# Connectors.net
KiCad netlist of a schematic drawn in Altium Designer
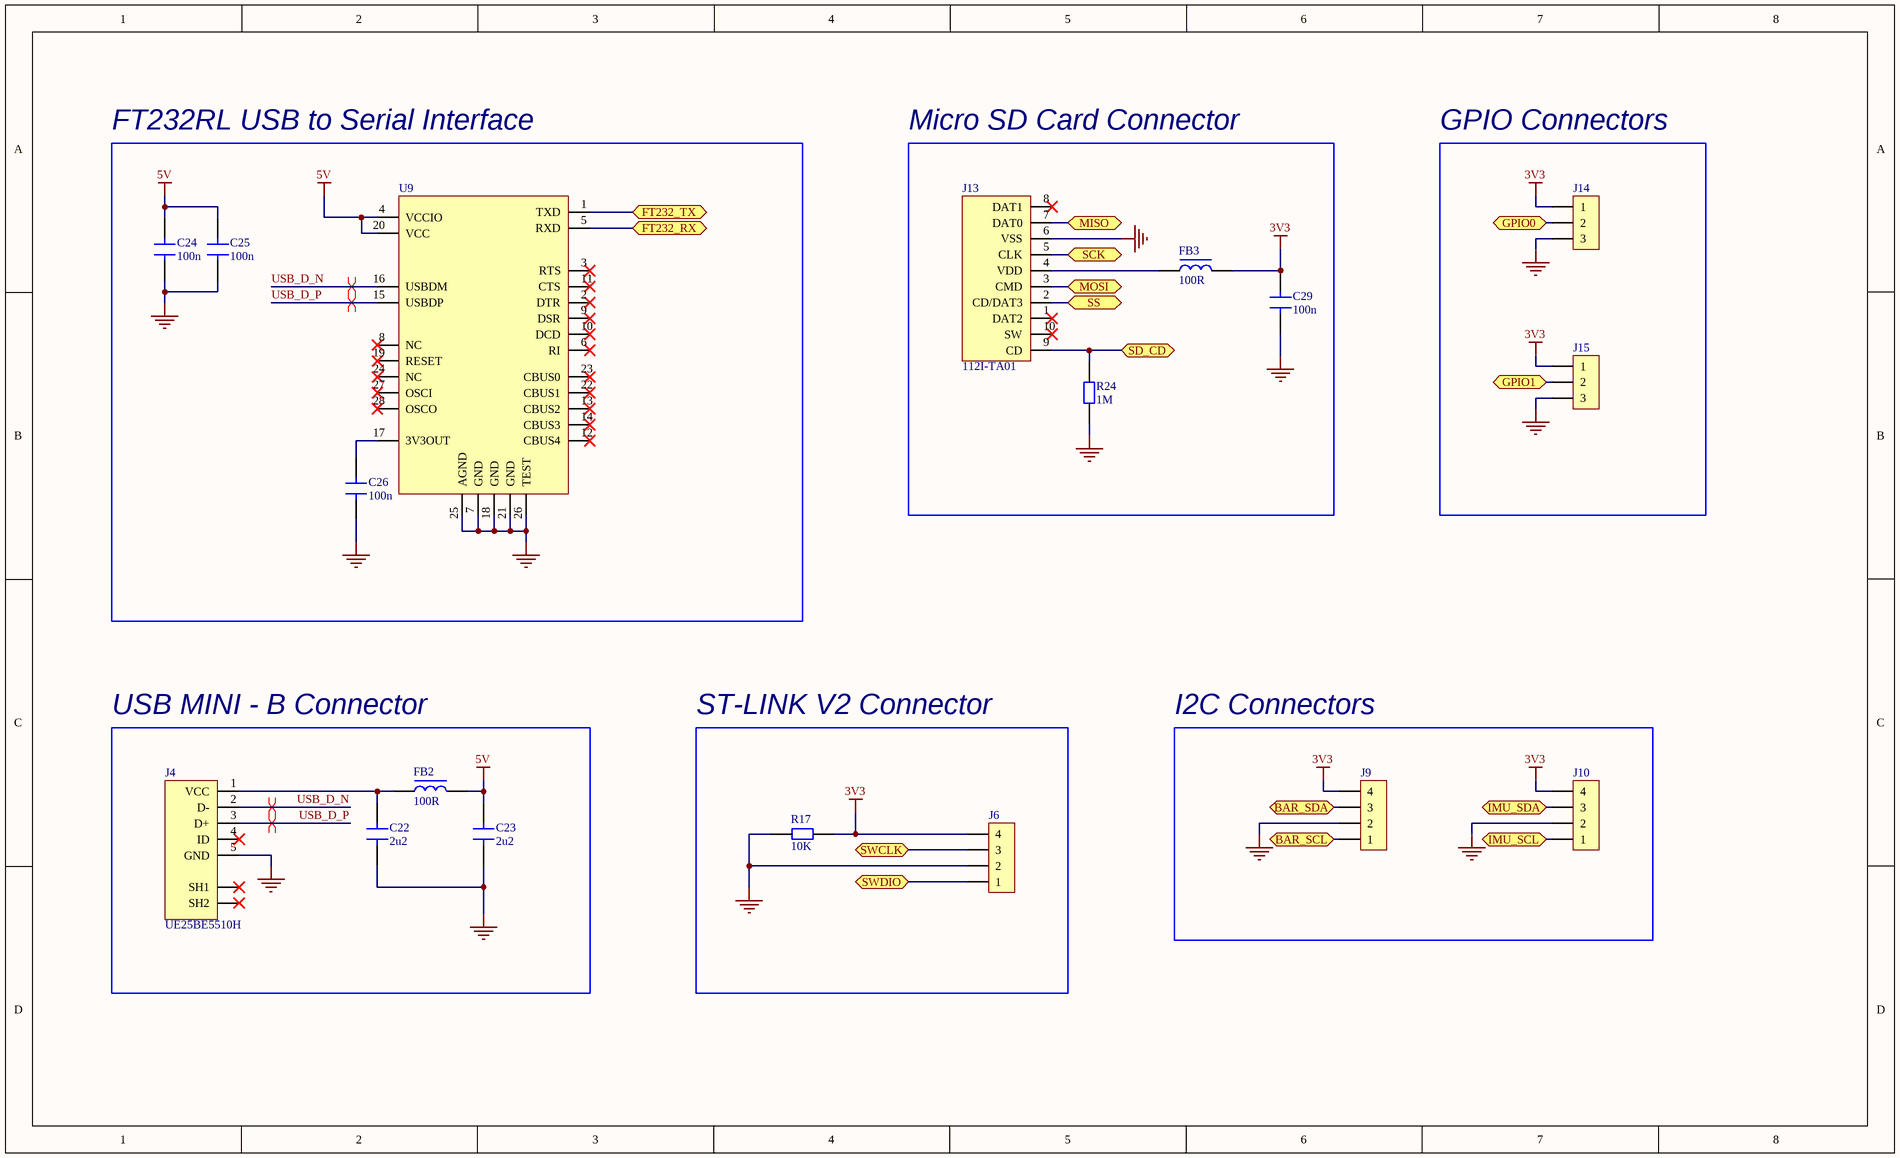
[diagram p0: Connectors.SchDoc]

(export (version "E")
  (design (tool "Eeschema 10.0.6"))
  (components
    (comp (ref "C22")
      (value "2u2")
      (footprint "CAP 0805")
      (description "Capacitor SMD 0805 25V")
      (libsource (lib "Schlib") (part "CAP 0805 25V"))
    )
    (comp (ref "C23")
      (value "2u2")
      (footprint "CAP 0805")
      (description "Capacitor SMD 0805 25V")
      (libsource (lib "Schlib") (part "CAP 0805 25V"))
    )
    (comp (ref "C24")
      (value "100n")
      (footprint "CAP 0603")
      (description "Capacitor SMD 0603 50V")
      (libsource (lib "Schlib") (part "CAP 0603 50V"))
    )
    (comp (ref "C25")
      (value "100n")
      (footprint "CAP 0603")
      (description "Capacitor SMD 0603 50V")
      (libsource (lib "Schlib") (part "CAP 0603 50V"))
    )
    (comp (ref "C26")
      (value "100n")
      (footprint "CAP 0603")
      (description "Capacitor SMD 0603 50V")
      (libsource (lib "Schlib") (part "CAP 0603 50V"))
    )
    (comp (ref "C29")
      (value "100n")
      (footprint "CAP 0603")
      (description "Capacitor SMD 0603 50V")
      (libsource (lib "Schlib") (part "CAP 0603 50V"))
    )
    (comp (ref "FB2")
      (value "100R")
      (footprint "FB 0805")
      (description "Ferrite Bead SMD 0805")
      (libsource (lib "Schlib") (part "FB 0805"))
    )
    (comp (ref "FB3")
      (value "100R")
      (footprint "FB 0603")
      (description "Ferrite Bead SMD 0603")
      (libsource (lib "Schlib") (part "FB 0603"))
    )
    (comp (ref "J4")
      (value "UE25BE5510H")
      (footprint "UE25BE55H")
      (description "Conn Mini USB 2.0 Type B RCP 5 POS 0.8mm Solder ST Thru-Hole 5 Terminal 1 Port")
      (fields (field (name "MANUFACTURER") "Amphenol Commercial"))
      (libsource (lib "Schlib") (part "UE25BE5510H"))
    )
    (comp (ref "J6")
      (value "1x4 HEADER MALE")
      (footprint "1X4 HEADER MALE")
      (libsource (lib "Schlib") (part "1x4 HEADER MALE"))
    )
    (comp (ref "J9")
      (value "1x4 HEADER MALE")
      (footprint "1X4 HEADER MALE")
      (libsource (lib "Schlib") (part "1x4 HEADER MALE"))
    )
    (comp (ref "J10")
      (value "1x4 HEADER MALE")
      (footprint "1X4 HEADER MALE")
      (libsource (lib "Schlib") (part "1x4 HEADER MALE"))
    )
    (comp (ref "J13")
      (value "112I-TA01")
      (footprint "112I-TA01")
      (description "Micro SD Card Push-Pull 10P (8+2), Switch, Peg, SMD 112I-TA01")
      (libsource (lib "Schlib") (part "112I-TA01"))
    )
    (comp (ref "J14")
      (value "JST B3B-XH-A")
      (footprint "JST_B3B-XH-A")
      (description "Connector Header, XH Series, 3 Position, 2.50mm, Through Hole, Press-Fit, Solder, Natural")
      (fields
        (field (name "MANUFACTURER") "JST")
        (field (name "MANUFACTURER PART NUMBER") "B3B-XH-A(LF)(SN)")
      )
      (libsource (lib "Schlib") (part "JST B3B-XH-A"))
    )
    (comp (ref "J15")
      (value "JST B3B-XH-A")
      (footprint "JST_B3B-XH-A")
      (description "Connector Header, XH Series, 3 Position, 2.50mm, Through Hole, Press-Fit, Solder, Natural")
      (fields
        (field (name "MANUFACTURER") "JST")
        (field (name "MANUFACTURER PART NUMBER") "B3B-XH-A(LF)(SN)")
      )
      (libsource (lib "Schlib") (part "JST B3B-XH-A"))
    )
    (comp (ref "R17")
      (value "10K")
      (footprint "RES 0603")
      (description "Resistor SMD 0603")
      (libsource (lib "Schlib") (part "RES 0603"))
    )
    (comp (ref "R24")
      (value "1M")
      (footprint "RES 0603")
      (description "Resistor SMD 0603")
      (libsource (lib "Schlib") (part "RES 0603"))
    )
    (comp (ref "U9")
      (value "FT232RL-REEL")
      (footprint "FT232RL")
      (description "IC USB FS SERIAL UART 28-SSOP")
      (fields (field (name "MANUFACTURER") "FTDI") (field (name "VOLTAGE") "5V"))
      (libsource (lib "Schlib") (part "FT232RL-REEL"))
    )
  )
  (nets
    (net (code "1") (name "/BAR_SCL") (class "Default")
      (node (ref "J9") (pin "1") (pinfunction "1_1") (pintype "passive"))
    )
    (net (code "2") (name "/BAR_SDA") (class "Default")
      (node (ref "J9") (pin "3") (pinfunction "3_3") (pintype "passive"))
    )
    (net (code "3") (name "/FT232_RX") (class "Default")
      (node (ref "U9") (pin "5") (pinfunction "RXD_5") (pintype "passive"))
    )
    (net (code "4") (name "/FT232_TX") (class "Default")
      (node (ref "U9") (pin "1") (pinfunction "TXD_1") (pintype "passive"))
    )
    (net (code "5") (name "/GPIO0") (class "Default")
      (node (ref "J14") (pin "2") (pinfunction "2_2") (pintype "passive"))
    )
    (net (code "6") (name "/GPIO1") (class "Default")
      (node (ref "J15") (pin "2") (pinfunction "2_2") (pintype "passive"))
    )
    (net (code "7") (name "/IMU_SCL") (class "Default")
      (node (ref "J10") (pin "1") (pinfunction "1_1") (pintype "passive"))
    )
    (net (code "8") (name "/IMU_SDA") (class "Default")
      (node (ref "J10") (pin "3") (pinfunction "3_3") (pintype "passive"))
    )
    (net (code "9") (name "/MISO") (class "Default")
      (node (ref "J13") (pin "7") (pinfunction "DAT0_7") (pintype "passive"))
    )
    (net (code "10") (name "/MOSI") (class "Default")
      (node (ref "J13") (pin "3") (pinfunction "CMD_3") (pintype "passive"))
    )
    (net (code "11") (name "/SCK") (class "Default")
      (node (ref "J13") (pin "5") (pinfunction "CLK_5") (pintype "passive"))
    )
    (net (code "12") (name "/SD_CD") (class "Default")
      (node (ref "J13") (pin "9") (pinfunction "CD_9") (pintype "passive"))
      (node (ref "R24") (pin "2") (pinfunction "2_2") (pintype "passive"))
    )
    (net (code "13") (name "/SS") (class "Default")
      (node (ref "J13") (pin "2") (pinfunction "CD/DAT3_2") (pintype "passive"))
    )
    (net (code "14") (name "/SWCLK") (class "Default")
      (node (ref "J6") (pin "3") (pinfunction "3_3") (pintype "passive"))
    )
    (net (code "15") (name "/SWDIO") (class "Default")
      (node (ref "J6") (pin "1") (pinfunction "1_1") (pintype "passive"))
    )
    (net (code "16") (name "/USB_D_N") (class "Default")
      (node (ref "J4") (pin "2") (pinfunction "D-_2") (pintype "passive"))
      (node (ref "U9") (pin "16") (pinfunction "USBDM_16") (pintype "passive"))
    )
    (net (code "17") (name "/USB_D_P") (class "Default")
      (node (ref "J4") (pin "3") (pinfunction "D+_3") (pintype "passive"))
      (node (ref "U9") (pin "15") (pinfunction "USBDP_15") (pintype "passive"))
    )
    (net (code "18") (name "3V3") (class "Default")
      (node (ref "C29") (pin "2") (pinfunction "2_2") (pintype "passive"))
      (node (ref "FB3") (pin "2") (pintype "passive"))
      (node (ref "J10") (pin "4") (pinfunction "4_4") (pintype "passive"))
      (node (ref "J14") (pin "1") (pinfunction "1_1") (pintype "passive"))
      (node (ref "J15") (pin "1") (pinfunction "1_1") (pintype "passive"))
      (node (ref "J6") (pin "4") (pinfunction "4_4") (pintype "passive"))
      (node (ref "J9") (pin "4") (pinfunction "4_4") (pintype "passive"))
      (node (ref "R17") (pin "2") (pinfunction "2_2") (pintype "passive"))
    )
    (net (code "19") (name "5V") (class "Default")
      (node (ref "C23") (pin "2") (pinfunction "2_2") (pintype "passive"))
      (node (ref "C24") (pin "2") (pinfunction "2_2") (pintype "passive"))
      (node (ref "C25") (pin "2") (pinfunction "2_2") (pintype "passive"))
      (node (ref "FB2") (pin "2") (pintype "passive"))
      (node (ref "U9") (pin "20") (pinfunction "VCC_20") (pintype "passive"))
      (node (ref "U9") (pin "4") (pinfunction "VCCIO_4") (pintype "passive"))
    )
    (net (code "20") (name "GND") (class "Default")
      (node (ref "C22") (pin "1") (pinfunction "1_1") (pintype "passive"))
      (node (ref "C23") (pin "1") (pinfunction "1_1") (pintype "passive"))
      (node (ref "C24") (pin "1") (pinfunction "1_1") (pintype "passive"))
      (node (ref "C25") (pin "1") (pinfunction "1_1") (pintype "passive"))
      (node (ref "C26") (pin "1") (pinfunction "1_1") (pintype "passive"))
      (node (ref "C29") (pin "1") (pinfunction "1_1") (pintype "passive"))
      (node (ref "J10") (pin "2") (pinfunction "2_2") (pintype "passive"))
      (node (ref "J13") (pin "6") (pinfunction "VSS_6") (pintype "passive"))
      (node (ref "J14") (pin "3") (pinfunction "3_3") (pintype "passive"))
      (node (ref "J15") (pin "3") (pinfunction "3_3") (pintype "passive"))
      (node (ref "J4") (pin "5") (pinfunction "GND_5") (pintype "passive"))
      (node (ref "J6") (pin "2") (pinfunction "2_2") (pintype "passive"))
      (node (ref "J9") (pin "2") (pinfunction "2_2") (pintype "passive"))
      (node (ref "R17") (pin "1") (pinfunction "1_1") (pintype "passive"))
      (node (ref "R24") (pin "1") (pinfunction "1_1") (pintype "passive"))
      (node (ref "U9") (pin "18") (pinfunction "GND_18") (pintype "passive"))
      (node (ref "U9") (pin "21") (pinfunction "GND_21") (pintype "passive"))
      (node (ref "U9") (pin "25") (pinfunction "AGND_25") (pintype "passive"))
      (node (ref "U9") (pin "26") (pinfunction "TEST_26") (pintype "passive"))
      (node (ref "U9") (pin "7") (pinfunction "GND_7") (pintype "passive"))
    )
    (net (code "21") (name "Net-(J4-VCC)") (class "Default")
      (node (ref "C22") (pin "2") (pinfunction "2_2") (pintype "passive"))
      (node (ref "FB2") (pin "1") (pintype "passive"))
      (node (ref "J4") (pin "1") (pinfunction "VCC_1") (pintype "passive"))
    )
    (net (code "22") (name "Net-(J13-VDD)") (class "Default")
      (node (ref "FB3") (pin "1") (pintype "passive"))
      (node (ref "J13") (pin "4") (pinfunction "VDD_4") (pintype "passive"))
    )
    (net (code "23") (name "Net-(U9-3V3OUT)") (class "Default")
      (node (ref "C26") (pin "2") (pinfunction "2_2") (pintype "passive"))
      (node (ref "U9") (pin "17") (pinfunction "3V3OUT_17") (pintype "passive"))
    )
    (net (code "24") (name "unconnected-(J4-ID-Pad4)") (class "Default")
      (node (ref "J4") (pin "4") (pinfunction "ID_4") (pintype "passive+no_connect"))
    )
    (net (code "25") (name "unconnected-(J4-PadSH1)") (class "Default")
      (node (ref "J4") (pin "SH1") (pinfunction "SH1_SH1") (pintype "passive+no_connect"))
    )
    (net (code "26") (name "unconnected-(J4-PadSH2)") (class "Default")
      (node (ref "J4") (pin "SH2") (pinfunction "SH2_SH2") (pintype "passive+no_connect"))
    )
    (net (code "27") (name "unconnected-(J13-DAT1-Pad8)") (class "Default")
      (node (ref "J13") (pin "8") (pinfunction "DAT1_8") (pintype "passive+no_connect"))
    )
    (net (code "28") (name "unconnected-(J13-DAT2-Pad1)") (class "Default")
      (node (ref "J13") (pin "1") (pinfunction "DAT2_1") (pintype "passive+no_connect"))
    )
    (net (code "29") (name "unconnected-(J13-SW-Pad10)") (class "Default")
      (node (ref "J13") (pin "10") (pinfunction "SW_10") (pintype "passive+no_connect"))
    )
    (net (code "30") (name "unconnected-(U9-CBUS0-Pad23)") (class "Default")
      (node (ref "U9") (pin "23") (pinfunction "CBUS0_23") (pintype "passive+no_connect"))
    )
    (net (code "31") (name "unconnected-(U9-CBUS1-Pad22)") (class "Default")
      (node (ref "U9") (pin "22") (pinfunction "CBUS1_22") (pintype "passive+no_connect"))
    )
    (net (code "32") (name "unconnected-(U9-CBUS2-Pad13)") (class "Default")
      (node (ref "U9") (pin "13") (pinfunction "CBUS2_13") (pintype "passive+no_connect"))
    )
    (net (code "33") (name "unconnected-(U9-CBUS3-Pad14)") (class "Default")
      (node (ref "U9") (pin "14") (pinfunction "CBUS3_14") (pintype "passive+no_connect"))
    )
    (net (code "34") (name "unconnected-(U9-CBUS4-Pad12)") (class "Default")
      (node (ref "U9") (pin "12") (pinfunction "CBUS4_12") (pintype "passive+no_connect"))
    )
    (net (code "35") (name "unconnected-(U9-CTS-Pad11)") (class "Default")
      (node (ref "U9") (pin "11") (pinfunction "CTS_11") (pintype "passive+no_connect"))
    )
    (net (code "36") (name "unconnected-(U9-DCD-Pad10)") (class "Default")
      (node (ref "U9") (pin "10") (pinfunction "DCD_10") (pintype "passive+no_connect"))
    )
    (net (code "37") (name "unconnected-(U9-DSR-Pad9)") (class "Default")
      (node (ref "U9") (pin "9") (pinfunction "DSR_9") (pintype "passive+no_connect"))
    )
    (net (code "38") (name "unconnected-(U9-DTR-Pad2)") (class "Default")
      (node (ref "U9") (pin "2") (pinfunction "DTR_2") (pintype "passive+no_connect"))
    )
    (net (code "39") (name "unconnected-(U9-NC-Pad8)") (class "Default")
      (node (ref "U9") (pin "8") (pinfunction "NC_8") (pintype "passive+no_connect"))
    )
    (net (code "40") (name "unconnected-(U9-NC-Pad24)") (class "Default")
      (node (ref "U9") (pin "24") (pinfunction "NC_24") (pintype "passive+no_connect"))
    )
    (net (code "41") (name "unconnected-(U9-OSCI-Pad27)") (class "Default")
      (node (ref "U9") (pin "27") (pinfunction "OSCI_27") (pintype "passive+no_connect"))
    )
    (net (code "42") (name "unconnected-(U9-OSCO-Pad28)") (class "Default")
      (node (ref "U9") (pin "28") (pinfunction "OSCO_28") (pintype "passive+no_connect"))
    )
    (net (code "43") (name "unconnected-(U9-RESET-Pad19)") (class "Default")
      (node (ref "U9") (pin "19") (pinfunction "RESET_19") (pintype "passive+no_connect"))
    )
    (net (code "44") (name "unconnected-(U9-RI-Pad6)") (class "Default")
      (node (ref "U9") (pin "6") (pinfunction "RI_6") (pintype "passive+no_connect"))
    )
    (net (code "45") (name "unconnected-(U9-RTS-Pad3)") (class "Default")
      (node (ref "U9") (pin "3") (pinfunction "RTS_3") (pintype "passive+no_connect"))
    )
  )
)
